# d11toy2d.net
KiCad netlist of a schematic drawn in EAGLE
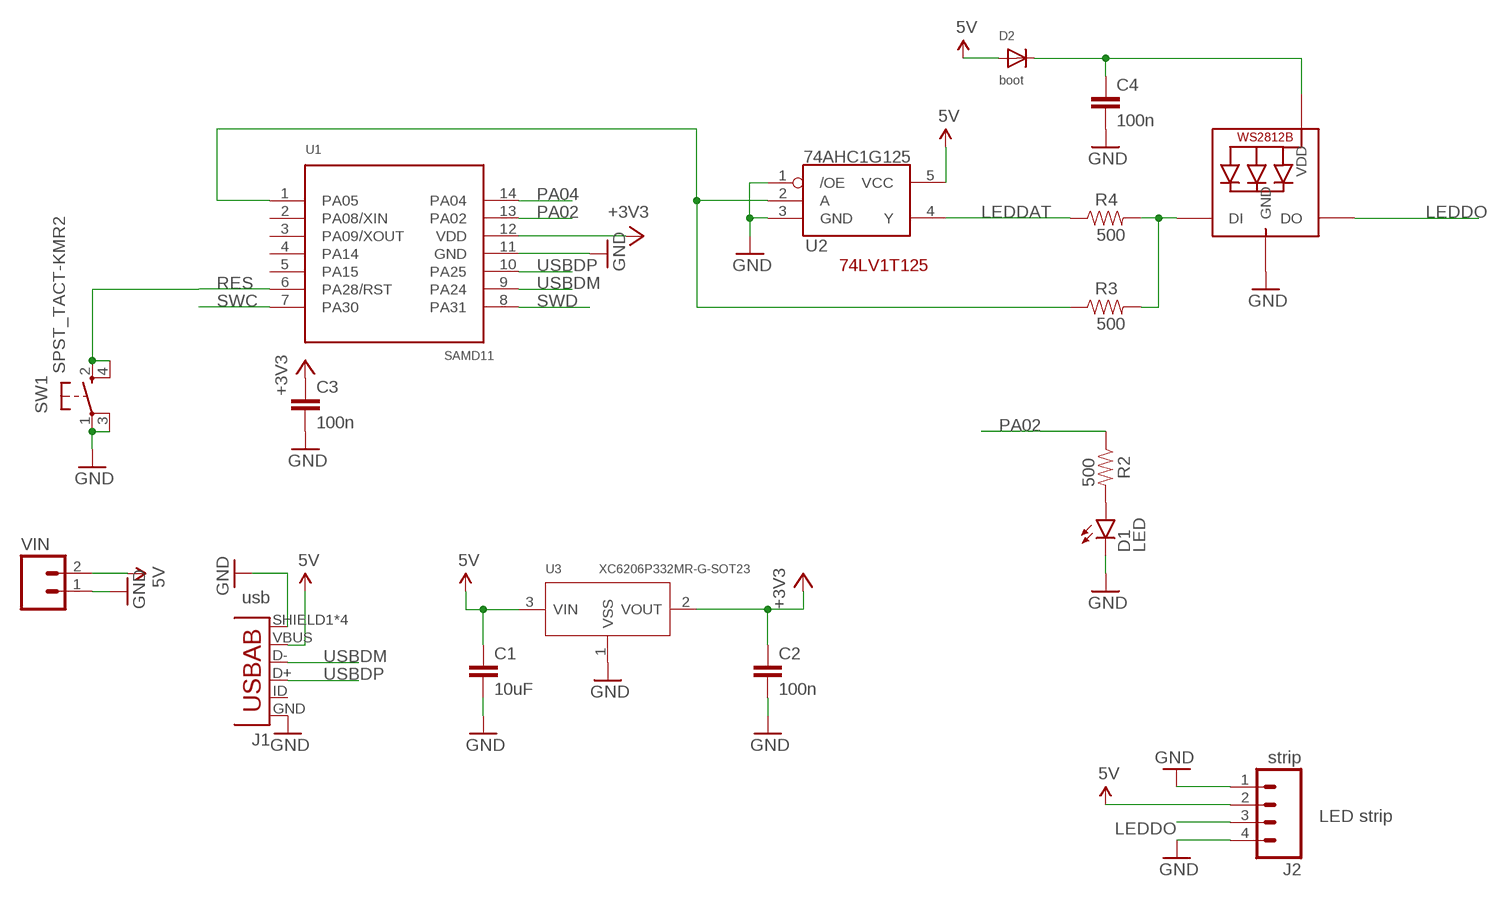
[diagram p0: schematic, sheet 1]

(export (version "E")
  (design (tool "Eeschema 10.0.6"))
  (components
    (comp (ref "C1")
      (value "10uF")
      (footprint "eagle-import:0603-CAP")
      (libsource (lib "eagle-import") (part "CAP0603-CAP"))
    )
    (comp (ref "C2")
      (value "100n")
      (footprint "eagle-import:0603-CAP")
      (libsource (lib "eagle-import") (part "CAP0603-CAP"))
    )
    (comp (ref "C3")
      (value "100n")
      (footprint "eagle-import:0603-CAP")
      (libsource (lib "eagle-import") (part "CAP0603-CAP"))
    )
    (comp (ref "C4")
      (value "100n")
      (footprint "eagle-import:0603-CAP")
      (libsource (lib "eagle-import") (part "CAP0603-CAP"))
    )
    (comp (ref "D1")
      (value "LED")
      (footprint "eagle-import:LED-0603")
      (libsource (lib "eagle-import") (part "LED0603"))
    )
    (comp (ref "D2")
      (value "boot")
      (footprint "eagle-import:SOD-523")
      (libsource (lib "eagle-import") (part "DIODESOD-523"))
    )
    (comp (ref "J1")
      (value "usb")
      (footprint "eagle-import:USB-AB-MICRO-SMD")
      (libsource (lib "eagle-import") (part "USB-AB"))
    )
    (comp (ref "J2")
      (value "strip")
      (footprint "eagle-import:1X04_NO_SILK_ALL_ROUND")
      (libsource (lib "eagle-import") (part "M04NO_SILK_ALL_ROUND"))
    )
    (comp (ref "LED1")
      (value "WS2812B5050")
      (footprint "eagle-import:WS2812B")
      (libsource (lib "eagle-import") (part "WS2812B5050"))
    )
    (comp (ref "R2")
      (value "500")
      (footprint "eagle-import:0603-RES")
      (libsource (lib "eagle-import") (part "RESISTOR0603-RES"))
    )
    (comp (ref "R3")
      (value "500")
      (footprint "eagle-import:0603-RES")
      (libsource (lib "eagle-import") (part "RESISTOR0603-RES"))
    )
    (comp (ref "R4")
      (value "500")
      (footprint "eagle-import:0603-RES")
      (libsource (lib "eagle-import") (part "RESISTOR0603-RES"))
    )
    (comp (ref "SW1")
      (value "SPST_TACT-KMR2")
      (footprint "eagle-import:KMR2")
      (libsource (lib "eagle-import") (part "SPST_TACT-KMR2"))
    )
    (comp (ref "U1")
      (value "SAMD11")
      (footprint "eagle-import:SO14")
      (libsource (lib "eagle-import") (part "SAMD11C14"))
    )
    (comp (ref "U2")
      (value "74AHC1G125")
      (footprint "eagle-import:SOT23-5")
      (libsource (lib "eagle-import") (part "74AHC1G125"))
    )
    (comp (ref "U3")
      (value "XC6206P332MR-G-SOT23")
      (footprint "eagle-import:SOT-23")
      (fields (field (name "MPN") "XC6206P332MR-G"))
      (libsource (lib "eagle-import") (part "PMIC-LDO-XC6206P332MR-G(SOT23)"))
    )
    (comp (ref "VIN")
      (value "M02PTH")
      (footprint "eagle-import:1X02")
      (libsource (lib "eagle-import") (part "M02PTH"))
    )
  )
  (nets
    (net (code "1") (name "+3V3") (class "Default")
      (node (ref "C2") (pin "1") (pinfunction "1_1") (pintype "passive"))
      (node (ref "C3") (pin "1") (pinfunction "1_1") (pintype "passive"))
      (node (ref "U1") (pin "12") (pinfunction "VDD_12") (pintype "bidirectional"))
      (node (ref "U3") (pin "2") (pinfunction "VOUT_2") (pintype "output"))
    )
    (net (code "2") (name "/LEDDAT") (class "Default")
      (node (ref "R4") (pin "1") (pinfunction "1_1") (pintype "passive"))
      (node (ref "U2") (pin "4") (pinfunction "Y_4") (pintype "bidirectional"))
    )
    (net (code "3") (name "/LEDDO") (class "Default")
      (node (ref "J2") (pin "3") (pinfunction "3_3") (pintype "passive"))
      (node (ref "LED1") (pin "2-DOUT") (pinfunction "DO_2-DOUT") (pintype "output"))
    )
    (net (code "4") (name "/PA02") (class "Default")
      (node (ref "R2") (pin "1") (pinfunction "1_1") (pintype "passive"))
      (node (ref "U1") (pin "13") (pinfunction "PA02_13") (pintype "bidirectional"))
    )
    (net (code "5") (name "/PA04") (class "Default")
      (node (ref "U1") (pin "14") (pinfunction "PA04_14") (pintype "bidirectional"))
    )
    (net (code "6") (name "/RES") (class "Default")
      (node (ref "SW1") (pin "2") (pinfunction "S_2") (pintype "passive"))
      (node (ref "SW1") (pin "4") (pinfunction "S1_4") (pintype "passive"))
      (node (ref "U1") (pin "6") (pinfunction "PA28/RST_6") (pintype "bidirectional"))
    )
    (net (code "7") (name "/SWC") (class "Default")
      (node (ref "U1") (pin "7") (pinfunction "PA30_7") (pintype "bidirectional"))
    )
    (net (code "8") (name "/SWD") (class "Default")
      (node (ref "U1") (pin "8") (pinfunction "PA31_8") (pintype "bidirectional"))
    )
    (net (code "9") (name "/USBDM") (class "Default")
      (node (ref "J1") (pin "D-") (pinfunction "D-_D-") (pintype "bidirectional"))
      (node (ref "U1") (pin "9") (pinfunction "PA24_9") (pintype "bidirectional"))
    )
    (net (code "10") (name "/USBDP") (class "Default")
      (node (ref "J1") (pin "D+") (pinfunction "D+_D+") (pintype "bidirectional"))
      (node (ref "U1") (pin "10") (pinfunction "PA25_10") (pintype "bidirectional"))
    )
    (net (code "11") (name "5V") (class "Default")
      (node (ref "C1") (pin "1") (pinfunction "1_1") (pintype "passive"))
      (node (ref "D2") (pin "A") (pinfunction "A_A") (pintype "passive"))
      (node (ref "J1") (pin "VBUS") (pinfunction "VBUS_VBUS") (pintype "bidirectional"))
      (node (ref "J2") (pin "2") (pinfunction "2_2") (pintype "passive"))
      (node (ref "U2") (pin "5") (pinfunction "VCC_5") (pintype "bidirectional"))
      (node (ref "U3") (pin "3") (pinfunction "VIN_3") (pintype "input"))
      (node (ref "VIN") (pin "2") (pinfunction "2_2") (pintype "passive"))
    )
    (net (code "12") (name "GND") (class "Default")
      (node (ref "C1") (pin "2") (pinfunction "2_2") (pintype "passive"))
      (node (ref "C2") (pin "2") (pinfunction "2_2") (pintype "passive"))
      (node (ref "C3") (pin "2") (pinfunction "2_2") (pintype "passive"))
      (node (ref "C4") (pin "2") (pinfunction "2_2") (pintype "passive"))
      (node (ref "D1") (pin "C") (pinfunction "C_C") (pintype "passive"))
      (node (ref "J1") (pin "GND") (pinfunction "GND_GND") (pintype "bidirectional"))
      (node (ref "J1") (pin "SHIELD1") (pinfunction "SHIELD_SHIELD1") (pintype "bidirectional"))
      (node (ref "J1") (pin "SHIELD2") (pinfunction "SHIELD_SHIELD2") (pintype "bidirectional"))
      (node (ref "J1") (pin "SHIELD3") (pinfunction "SHIELD_SHIELD3") (pintype "bidirectional"))
      (node (ref "J1") (pin "SHIELD4") (pinfunction "SHIELD_SHIELD4") (pintype "bidirectional"))
      (node (ref "J2") (pin "1") (pinfunction "1_1") (pintype "passive"))
      (node (ref "J2") (pin "4") (pinfunction "4_4") (pintype "passive"))
      (node (ref "LED1") (pin "3-GND") (pinfunction "GND_3-GND") (pintype "power_in"))
      (node (ref "SW1") (pin "1") (pinfunction "P_1") (pintype "passive"))
      (node (ref "SW1") (pin "3") (pinfunction "P1_3") (pintype "passive"))
      (node (ref "U1") (pin "11") (pinfunction "GND_11") (pintype "bidirectional"))
      (node (ref "U2") (pin "1") (pinfunction "/OE_1") (pintype "bidirectional"))
      (node (ref "U2") (pin "3") (pinfunction "GND_3") (pintype "bidirectional"))
      (node (ref "U3") (pin "1") (pinfunction "VSS_1") (pintype "power_in"))
      (node (ref "VIN") (pin "1") (pinfunction "1_1") (pintype "passive"))
    )
    (net (code "13") (name "Net-(D1-PadA)") (class "Default")
      (node (ref "D1") (pin "A") (pinfunction "A_A") (pintype "passive"))
      (node (ref "R2") (pin "2") (pinfunction "2_2") (pintype "passive"))
    )
    (net (code "14") (name "Net-(D2-C)") (class "Default")
      (node (ref "C4") (pin "1") (pinfunction "1_1") (pintype "passive"))
      (node (ref "D2") (pin "K") (pinfunction "C_K") (pintype "passive"))
      (node (ref "LED1") (pin "1-VDD") (pinfunction "VDD_1-VDD") (pintype "power_in"))
    )
    (net (code "15") (name "Net-(LED1-DI)") (class "Default")
      (node (ref "LED1") (pin "4-DIN") (pinfunction "DI_4-DIN") (pintype "input"))
      (node (ref "R3") (pin "2") (pinfunction "2_2") (pintype "passive"))
      (node (ref "R4") (pin "2") (pinfunction "2_2") (pintype "passive"))
    )
    (net (code "16") (name "Net-(U1-PA05)") (class "Default")
      (node (ref "R3") (pin "1") (pinfunction "1_1") (pintype "passive"))
      (node (ref "U1") (pin "1") (pinfunction "PA05_1") (pintype "bidirectional"))
      (node (ref "U2") (pin "2") (pinfunction "A_2") (pintype "bidirectional"))
    )
    (net (code "17") (name "unconnected-(J1-USBID-PadID)") (class "Default")
      (node (ref "J1") (pin "ID") (pinfunction "USBID_ID") (pintype "bidirectional"))
    )
    (net (code "18") (name "unconnected-(U1-PA08{slash}XIN-Pad2)") (class "Default")
      (node (ref "U1") (pin "2") (pinfunction "PA08/XIN_2") (pintype "bidirectional"))
    )
    (net (code "19") (name "unconnected-(U1-PA09{slash}XOUT-Pad3)") (class "Default")
      (node (ref "U1") (pin "3") (pinfunction "PA09/XOUT_3") (pintype "bidirectional"))
    )
    (net (code "20") (name "unconnected-(U1-PA14-Pad4)") (class "Default")
      (node (ref "U1") (pin "4") (pinfunction "PA14_4") (pintype "bidirectional"))
    )
    (net (code "21") (name "unconnected-(U1-PA15-Pad5)") (class "Default")
      (node (ref "U1") (pin "5") (pinfunction "PA15_5") (pintype "bidirectional"))
    )
  )
)
